# Module_AFE_FPC.net
KiCad netlist of a schematic drawn in Altium Designer
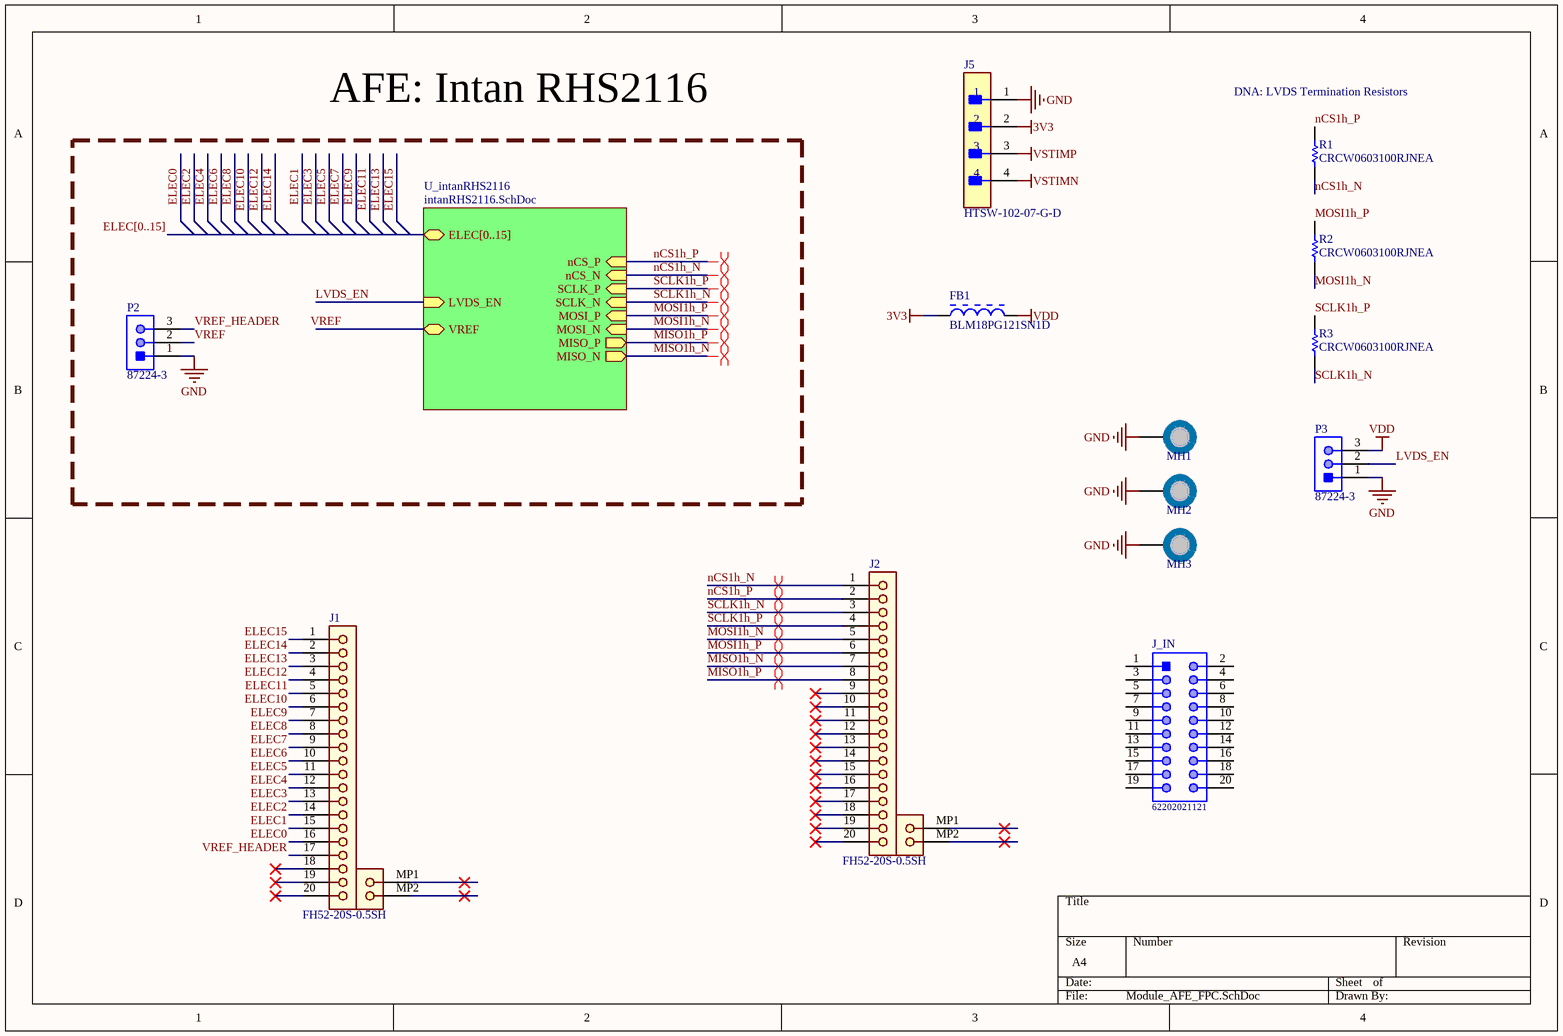
[diagram p0: Module_AFE_FPC.SchDoc]

(export (version "E")
  (design (tool "Eeschema 10.0.6"))
  (components
    (comp (ref "FB1")
      (value "BLM18PG121SN1D")
      (footprint "MURA-BLM18PG_KG-B25-CHIP-2_V1")
      (fields (field (name "MANUFACTURER") "Murata"))
      (libsource (lib "Altium Content Vault") (part "MURA-FB-2"))
    )
    (comp (ref "J1")
      (value "FH52-20S-0.5SH")
      (footprint "FH52-20S-0.5SH")
      (description "01X20 Terminal Connector with  2 mount ground pads")
      (fields (field (name "MANUFACTURER PN") "FH52-20S-0.5SH") (field (name "MANUFACTURER") "Hirose"))
      (libsource (lib "hirose_electric_fpc_ffc_connectors") (part "FH52-20S-0.5SH"))
    )
    (comp (ref "J2")
      (value "FH52-20S-0.5SH")
      (footprint "FH52-20S-0.5SH")
      (description "01X20 Terminal Connector with  2 mount ground pads")
      (fields (field (name "MANUFACTURER PN") "FH52-20S-0.5SH") (field (name "MANUFACTURER") "Hirose"))
      (libsource (lib "hirose_electric_fpc_ffc_connectors") (part "FH52-20S-0.5SH"))
    )
    (comp (ref "J5")
      (value "HTSW-102-07-G-D")
      (footprint "FP-HTSW-102-07-G-D-MFG")
      (description "CONN HEADER VERT 4POS 2.54MM")
      (fields
        (field (name "MANUFACTURER") "Samtec")
        (field (name "OCTOPART") "https://octopart.com/htsw-102-07-g-d-samtec-10531767")
      )
      (libsource (lib "Altium Content Vault") (part "299a8cea1bdcbc3624fe62c390fa72c"))
    )
    (comp (ref "J_IN")
      (value "62202021121")
      (footprint "62202021121")
      (description "THT Vertical Pin Header WR-PHD, Pitch 1.27 mm, Dual Row, 20 pins")
      (fields (field (name "MANUFACTURER") "Wurth Elektronik") (field (name "PUBLISHER") "WurthElektronik"))
      (libsource (lib "Altium Content Vault") (part "WE-CN-2P-M-R20"))
    )
    (comp (ref "MH1")
      (value "MH_7.4MMC_3.2MMD")
      (footprint "M2X0.4_plated_loose_fit_pan_head")
      (description "Mounting Hole 7.4mm Diameter, 3.2mm Drill")
      (libsource (lib "standard_components") (part "MH_7.4MMC_3.2MMC"))
    )
    (comp (ref "MH2")
      (value "MH_7.4MMC_3.2MMD")
      (footprint "M2X0.4_plated_loose_fit_pan_head")
      (description "Mounting Hole 7.4mm Diameter, 3.2mm Drill")
      (libsource (lib "standard_components") (part "MH_7.4MMC_3.2MMC"))
    )
    (comp (ref "MH3")
      (value "MH_7.4MMC_3.2MMD")
      (footprint "M2X0.4_plated_loose_fit_pan_head")
      (description "Mounting Hole 7.4mm Diameter, 3.2mm Drill")
      (libsource (lib "standard_components") (part "MH_7.4MMC_3.2MMC"))
    )
    (comp (ref "P2")
      (value "87224-3")
      (footprint "TECO-87224-3_V")
      (fields (field (name "MANUFACTURER") "TE Connectivity"))
      (libsource (lib "Altium Content Vault") (part "CN-1P-M-R3"))
    )
    (comp (ref "P3")
      (value "87224-3")
      (footprint "TECO-87224-3_V")
      (fields (field (name "MANUFACTURER") "TE Connectivity"))
      (libsource (lib "Altium Content Vault") (part "CN-1P-M-R3"))
    )
    (comp (ref "R1")
      (value "CRCW0603100RJNEA")
      (footprint "RESC1609X50X30ML10T20")
      (fields (field (name "MANUFACTURER") "Vishay Dale"))
      (libsource (lib "Altium Content Vault") (part "RES"))
    )
    (comp (ref "R2")
      (value "CRCW0603100RJNEA")
      (footprint "RESC1609X50X30ML10T20")
      (fields (field (name "MANUFACTURER") "Vishay Dale"))
      (libsource (lib "Altium Content Vault") (part "RES"))
    )
    (comp (ref "R3")
      (value "CRCW0603100RJNEA")
      (footprint "RESC1609X50X30ML10T20")
      (fields (field (name "MANUFACTURER") "Vishay Dale"))
      (libsource (lib "Altium Content Vault") (part "RES"))
    )
  )
  (nets
    (net (code "1") (name "/ELEC0") (class "Default")
      (node (ref "J1") (pin "16") (pinfunction "16_16") (pintype "passive"))
    )
    (net (code "2") (name "/ELEC1") (class "Default")
      (node (ref "J1") (pin "15") (pinfunction "15_15") (pintype "passive"))
    )
    (net (code "3") (name "/ELEC2") (class "Default")
      (node (ref "J1") (pin "14") (pinfunction "14_14") (pintype "passive"))
    )
    (net (code "4") (name "/ELEC3") (class "Default")
      (node (ref "J1") (pin "13") (pinfunction "13_13") (pintype "passive"))
    )
    (net (code "5") (name "/ELEC4") (class "Default")
      (node (ref "J1") (pin "12") (pinfunction "12_12") (pintype "passive"))
    )
    (net (code "6") (name "/ELEC5") (class "Default")
      (node (ref "J1") (pin "11") (pinfunction "11_11") (pintype "passive"))
    )
    (net (code "7") (name "/ELEC6") (class "Default")
      (node (ref "J1") (pin "10") (pinfunction "10_10") (pintype "passive"))
    )
    (net (code "8") (name "/ELEC7") (class "Default")
      (node (ref "J1") (pin "9") (pinfunction "9_9") (pintype "passive"))
    )
    (net (code "9") (name "/ELEC8") (class "Default")
      (node (ref "J1") (pin "8") (pinfunction "8_8") (pintype "passive"))
    )
    (net (code "10") (name "/ELEC9") (class "Default")
      (node (ref "J1") (pin "7") (pinfunction "7_7") (pintype "passive"))
    )
    (net (code "11") (name "/ELEC10") (class "Default")
      (node (ref "J1") (pin "6") (pinfunction "6_6") (pintype "passive"))
    )
    (net (code "12") (name "/ELEC11") (class "Default")
      (node (ref "J1") (pin "5") (pinfunction "5_5") (pintype "passive"))
    )
    (net (code "13") (name "/ELEC12") (class "Default")
      (node (ref "J1") (pin "4") (pinfunction "4_4") (pintype "passive"))
    )
    (net (code "14") (name "/ELEC13") (class "Default")
      (node (ref "J1") (pin "3") (pinfunction "3_3") (pintype "passive"))
    )
    (net (code "15") (name "/ELEC14") (class "Default")
      (node (ref "J1") (pin "2") (pinfunction "2_2") (pintype "passive"))
    )
    (net (code "16") (name "/ELEC15") (class "Default")
      (node (ref "J1") (pin "1") (pinfunction "1_1") (pintype "passive"))
    )
    (net (code "18") (name "/LVDS_EN") (class "Default")
      (node (ref "P3") (pin "2") (pinfunction "2_2") (pintype "passive"))
    )
    (net (code "19") (name "/MISO1h_N") (class "Default")
      (node (ref "J2") (pin "7") (pinfunction "7_7") (pintype "passive"))
    )
    (net (code "20") (name "/MISO1h_P") (class "Default")
      (node (ref "J2") (pin "8") (pinfunction "8_8") (pintype "passive"))
    )
    (net (code "21") (name "/MOSI1h_N") (class "Default")
      (node (ref "J2") (pin "5") (pinfunction "5_5") (pintype "passive"))
      (node (ref "R2") (pin "1") (pinfunction "1_1") (pintype "passive"))
    )
    (net (code "22") (name "/MOSI1h_P") (class "Default")
      (node (ref "J2") (pin "6") (pinfunction "6_6") (pintype "passive"))
      (node (ref "R2") (pin "2") (pinfunction "2_2") (pintype "passive"))
    )
    (net (code "23") (name "/SCLK1h_N") (class "Default")
      (node (ref "J2") (pin "3") (pinfunction "3_3") (pintype "passive"))
      (node (ref "R3") (pin "1") (pinfunction "1_1") (pintype "passive"))
    )
    (net (code "24") (name "/SCLK1h_P") (class "Default")
      (node (ref "J2") (pin "4") (pinfunction "4_4") (pintype "passive"))
      (node (ref "R3") (pin "2") (pinfunction "2_2") (pintype "passive"))
    )
    (net (code "25") (name "/VREF") (class "Default")
      (node (ref "P2") (pin "2") (pinfunction "2_2") (pintype "passive"))
    )
    (net (code "26") (name "/VREF_HEADER") (class "Default")
      (node (ref "J1") (pin "17") (pinfunction "17_17") (pintype "passive"))
      (node (ref "P2") (pin "3") (pinfunction "3_3") (pintype "passive"))
    )
    (net (code "27") (name "/nCS1h_N") (class "Default")
      (node (ref "J2") (pin "1") (pinfunction "1_1") (pintype "passive"))
      (node (ref "R1") (pin "1") (pinfunction "1_1") (pintype "passive"))
    )
    (net (code "28") (name "/nCS1h_P") (class "Default")
      (node (ref "J2") (pin "2") (pinfunction "2_2") (pintype "passive"))
      (node (ref "R1") (pin "2") (pinfunction "2_2") (pintype "passive"))
    )
    (net (code "29") (name "3V3") (class "Default")
      (node (ref "FB1") (pin "1") (pinfunction "1_1") (pintype "passive"))
      (node (ref "J5") (pin "2") (pinfunction "2_2") (pintype "passive"))
    )
    (net (code "30") (name "GND") (class "Default")
      (node (ref "J5") (pin "1") (pinfunction "1_1") (pintype "passive"))
      (node (ref "MH1") (pin "1") (pinfunction "1_1") (pintype "passive"))
      (node (ref "MH2") (pin "1") (pinfunction "1_1") (pintype "passive"))
      (node (ref "MH3") (pin "1") (pinfunction "1_1") (pintype "passive"))
      (node (ref "P2") (pin "1") (pinfunction "1_1") (pintype "passive"))
      (node (ref "P3") (pin "1") (pinfunction "1_1") (pintype "passive"))
    )
    (net (code "31") (name "VDD") (class "Default")
      (node (ref "FB1") (pin "2") (pinfunction "2_2") (pintype "passive"))
      (node (ref "P3") (pin "3") (pinfunction "3_3") (pintype "passive"))
    )
    (net (code "32") (name "VSTIMN") (class "Default")
      (node (ref "J5") (pin "4") (pinfunction "4_4") (pintype "passive"))
    )
    (net (code "33") (name "VSTIMP") (class "Default")
      (node (ref "J5") (pin "3") (pinfunction "3_3") (pintype "passive"))
    )
    (net (code "34") (name "unconnected-(J1-Pad18)") (class "Default")
      (node (ref "J1") (pin "18") (pinfunction "18_18") (pintype "passive+no_connect"))
    )
    (net (code "35") (name "unconnected-(J1-Pad19)") (class "Default")
      (node (ref "J1") (pin "19") (pinfunction "19_19") (pintype "passive+no_connect"))
    )
    (net (code "36") (name "unconnected-(J1-Pad20)") (class "Default")
      (node (ref "J1") (pin "20") (pinfunction "20_20") (pintype "passive+no_connect"))
    )
    (net (code "37") (name "unconnected-(J1-PadMP1)") (class "Default")
      (node (ref "J1") (pin "MP1") (pinfunction "MP1_MP1") (pintype "passive"))
    )
    (net (code "38") (name "unconnected-(J1-PadMP2)") (class "Default")
      (node (ref "J1") (pin "MP2") (pinfunction "MP2_MP2") (pintype "passive"))
    )
    (net (code "39") (name "unconnected-(J2-Pad9)") (class "Default")
      (node (ref "J2") (pin "9") (pinfunction "9_9") (pintype "passive+no_connect"))
    )
    (net (code "40") (name "unconnected-(J2-Pad10)") (class "Default")
      (node (ref "J2") (pin "10") (pinfunction "10_10") (pintype "passive+no_connect"))
    )
    (net (code "41") (name "unconnected-(J2-Pad11)") (class "Default")
      (node (ref "J2") (pin "11") (pinfunction "11_11") (pintype "passive+no_connect"))
    )
    (net (code "42") (name "unconnected-(J2-Pad12)") (class "Default")
      (node (ref "J2") (pin "12") (pinfunction "12_12") (pintype "passive+no_connect"))
    )
    (net (code "43") (name "unconnected-(J2-Pad13)") (class "Default")
      (node (ref "J2") (pin "13") (pinfunction "13_13") (pintype "passive+no_connect"))
    )
    (net (code "44") (name "unconnected-(J2-Pad14)") (class "Default")
      (node (ref "J2") (pin "14") (pinfunction "14_14") (pintype "passive+no_connect"))
    )
    (net (code "45") (name "unconnected-(J2-Pad15)") (class "Default")
      (node (ref "J2") (pin "15") (pinfunction "15_15") (pintype "passive+no_connect"))
    )
    (net (code "46") (name "unconnected-(J2-Pad16)") (class "Default")
      (node (ref "J2") (pin "16") (pinfunction "16_16") (pintype "passive+no_connect"))
    )
    (net (code "47") (name "unconnected-(J2-Pad17)") (class "Default")
      (node (ref "J2") (pin "17") (pinfunction "17_17") (pintype "passive+no_connect"))
    )
    (net (code "48") (name "unconnected-(J2-Pad18)") (class "Default")
      (node (ref "J2") (pin "18") (pinfunction "18_18") (pintype "passive+no_connect"))
    )
    (net (code "49") (name "unconnected-(J2-Pad19)") (class "Default")
      (node (ref "J2") (pin "19") (pinfunction "19_19") (pintype "passive+no_connect"))
    )
    (net (code "50") (name "unconnected-(J2-Pad20)") (class "Default")
      (node (ref "J2") (pin "20") (pinfunction "20_20") (pintype "passive+no_connect"))
    )
    (net (code "51") (name "unconnected-(J2-PadMP1)") (class "Default")
      (node (ref "J2") (pin "MP1") (pinfunction "MP1_MP1") (pintype "passive"))
    )
    (net (code "52") (name "unconnected-(J2-PadMP2)") (class "Default")
      (node (ref "J2") (pin "MP2") (pinfunction "MP2_MP2") (pintype "passive"))
    )
    (net (code "53") (name "unconnected-(J_IN-Pad1)") (class "Default")
      (node (ref "J_IN") (pin "1") (pinfunction "1_1") (pintype "passive"))
    )
    (net (code "54") (name "unconnected-(J_IN-Pad2)") (class "Default")
      (node (ref "J_IN") (pin "2") (pinfunction "2_2") (pintype "passive"))
    )
    (net (code "55") (name "unconnected-(J_IN-Pad3)") (class "Default")
      (node (ref "J_IN") (pin "3") (pinfunction "3_3") (pintype "passive"))
    )
    (net (code "56") (name "unconnected-(J_IN-Pad4)") (class "Default")
      (node (ref "J_IN") (pin "4") (pinfunction "4_4") (pintype "passive"))
    )
    (net (code "57") (name "unconnected-(J_IN-Pad5)") (class "Default")
      (node (ref "J_IN") (pin "5") (pinfunction "5_5") (pintype "passive"))
    )
    (net (code "58") (name "unconnected-(J_IN-Pad6)") (class "Default")
      (node (ref "J_IN") (pin "6") (pinfunction "6_6") (pintype "passive"))
    )
    (net (code "59") (name "unconnected-(J_IN-Pad7)") (class "Default")
      (node (ref "J_IN") (pin "7") (pinfunction "7_7") (pintype "passive"))
    )
    (net (code "60") (name "unconnected-(J_IN-Pad8)") (class "Default")
      (node (ref "J_IN") (pin "8") (pinfunction "8_8") (pintype "passive"))
    )
    (net (code "61") (name "unconnected-(J_IN-Pad9)") (class "Default")
      (node (ref "J_IN") (pin "9") (pinfunction "9_9") (pintype "passive"))
    )
    (net (code "62") (name "unconnected-(J_IN-Pad10)") (class "Default")
      (node (ref "J_IN") (pin "10") (pinfunction "10_10") (pintype "passive"))
    )
    (net (code "63") (name "unconnected-(J_IN-Pad11)") (class "Default")
      (node (ref "J_IN") (pin "11") (pinfunction "11_11") (pintype "passive"))
    )
    (net (code "64") (name "unconnected-(J_IN-Pad12)") (class "Default")
      (node (ref "J_IN") (pin "12") (pinfunction "12_12") (pintype "passive"))
    )
    (net (code "65") (name "unconnected-(J_IN-Pad13)") (class "Default")
      (node (ref "J_IN") (pin "13") (pinfunction "13_13") (pintype "passive"))
    )
    (net (code "66") (name "unconnected-(J_IN-Pad14)") (class "Default")
      (node (ref "J_IN") (pin "14") (pinfunction "14_14") (pintype "passive"))
    )
    (net (code "67") (name "unconnected-(J_IN-Pad15)") (class "Default")
      (node (ref "J_IN") (pin "15") (pinfunction "15_15") (pintype "passive"))
    )
    (net (code "68") (name "unconnected-(J_IN-Pad16)") (class "Default")
      (node (ref "J_IN") (pin "16") (pinfunction "16_16") (pintype "passive"))
    )
    (net (code "69") (name "unconnected-(J_IN-Pad17)") (class "Default")
      (node (ref "J_IN") (pin "17") (pinfunction "17_17") (pintype "passive"))
    )
    (net (code "70") (name "unconnected-(J_IN-Pad18)") (class "Default")
      (node (ref "J_IN") (pin "18") (pinfunction "18_18") (pintype "passive"))
    )
    (net (code "71") (name "unconnected-(J_IN-Pad19)") (class "Default")
      (node (ref "J_IN") (pin "19") (pinfunction "19_19") (pintype "passive"))
    )
    (net (code "72") (name "unconnected-(J_IN-Pad20)") (class "Default")
      (node (ref "J_IN") (pin "20") (pinfunction "20_20") (pintype "passive"))
    )
  )
)
